# DCtoAC_Schematic.net
KiCad netlist of a schematic drawn in Altium Designer
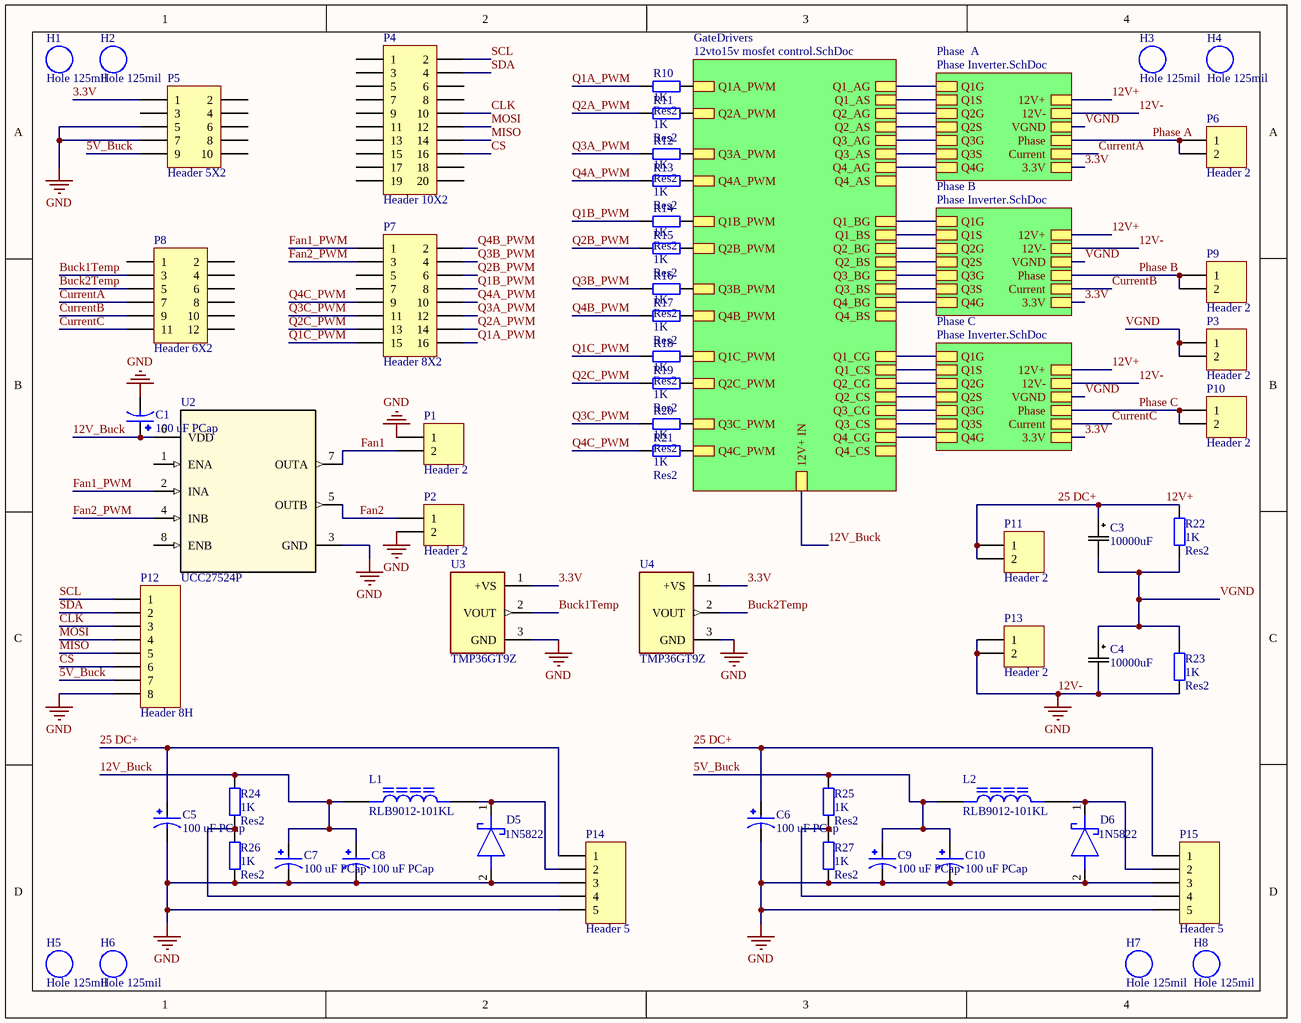
[diagram p0: DCtoAC Schematic.SchDoc]

(export (version "E")
  (design (tool "Eeschema 10.0.6"))
  (components
    (comp (ref "C1")
      (value "100 uF PCap")
      (footprint "Senior Design PCB Library:100uF PCap")
      (description "Capacitor; Aluminum Electrolytic; Radial Al Electrolytic Cap; 100uF 63V")
      (fields (field (name "MF") "Panasonic Electronic") (field (name "MP") "EEU-FC1J101"))
      (libsource (lib "") (part "100 uF PCap_1"))
    )
    (comp (ref "C3")
      (value "10000uF")
      (footprint "Senior Design PCB Library:CAP_UBY_18X35P5_NCH")
      (description "No Description Available")
      (libsource (lib "Senior Design Schematic Library") (part "10000uF"))
    )
    (comp (ref "C4")
      (value "10000uF")
      (footprint "Senior Design PCB Library:CAP_UBY_18X35P5_NCH")
      (description "No Description Available")
      (libsource (lib "Senior Design Schematic Library") (part "10000uF"))
    )
    (comp (ref "C5")
      (value "100 uF PCap")
      (footprint "Senior Design PCB Library:100uF PCap")
      (description "Capacitor; Aluminum Electrolytic; Radial Al Electrolytic Cap; 100uF 63V")
      (fields (field (name "MF") "Panasonic Electronic") (field (name "MP") "EEU-FC1J101"))
      (libsource (lib "Senior Design Schematic Library") (part "100 uF PCap"))
    )
    (comp (ref "C6")
      (value "100 uF PCap")
      (footprint "Senior Design PCB Library:100uF PCap")
      (description "Capacitor; Aluminum Electrolytic; Radial Al Electrolytic Cap; 100uF 63V")
      (fields (field (name "MF") "Panasonic Electronic") (field (name "MP") "EEU-FC1J101"))
      (libsource (lib "Senior Design Schematic Library") (part "100 uF PCap"))
    )
    (comp (ref "C7")
      (value "100 uF PCap")
      (footprint "Senior Design PCB Library:100uF PCap")
      (description "Capacitor; Aluminum Electrolytic; Radial Al Electrolytic Cap; 100uF 63V")
      (fields (field (name "MF") "Panasonic Electronic") (field (name "MP") "EEU-FC1J101"))
      (libsource (lib "Senior Design Schematic Library") (part "100 uF PCap"))
    )
    (comp (ref "C8")
      (value "100 uF PCap")
      (footprint "Senior Design PCB Library:100uF PCap")
      (description "Capacitor; Aluminum Electrolytic; Radial Al Electrolytic Cap; 100uF 63V")
      (fields (field (name "MF") "Panasonic Electronic") (field (name "MP") "EEU-FC1J101"))
      (libsource (lib "Senior Design Schematic Library") (part "100 uF PCap"))
    )
    (comp (ref "C9")
      (value "100 uF PCap")
      (footprint "Senior Design PCB Library:100uF PCap")
      (description "Capacitor; Aluminum Electrolytic; Radial Al Electrolytic Cap; 100uF 63V")
      (fields (field (name "MF") "Panasonic Electronic") (field (name "MP") "EEU-FC1J101"))
      (libsource (lib "Senior Design Schematic Library") (part "100 uF PCap"))
    )
    (comp (ref "C10")
      (value "100 uF PCap")
      (footprint "Senior Design PCB Library:100uF PCap")
      (description "Capacitor; Aluminum Electrolytic; Radial Al Electrolytic Cap; 100uF 63V")
      (fields (field (name "MF") "Panasonic Electronic") (field (name "MP") "EEU-FC1J101"))
      (libsource (lib "Senior Design Schematic Library") (part "100 uF PCap"))
    )
    (comp (ref "D5")
      (value "1N5822")
      (footprint "DIOAD3070W130L950D530")
      (description "Schottky Diode")
      (fields (field (name "MOUSER PART NUMBER") "511-1N5822"))
      (libsource (lib "Senior Design Schematic Library") (part "1N5822"))
    )
    (comp (ref "D6")
      (value "1N5822")
      (footprint "DIOAD3070W130L950D530")
      (description "Schottky Diode")
      (fields (field (name "MOUSER PART NUMBER") "511-1N5822"))
      (libsource (lib "Senior Design Schematic Library") (part "1N5822"))
    )
    (comp (ref "H1")
      (value "Hole 125mil")
      (footprint "Hole 125mil")
      (libsource (lib "ECE Lib 22") (part "Hole 125mil"))
    )
    (comp (ref "H2")
      (value "Hole 125mil")
      (footprint "Hole 125mil")
      (libsource (lib "ECE Lib 22") (part "Hole 125mil"))
    )
    (comp (ref "H3")
      (value "Hole 125mil")
      (footprint "Hole 125mil")
      (libsource (lib "ECE Lib 22") (part "Hole 125mil"))
    )
    (comp (ref "H4")
      (value "Hole 125mil")
      (footprint "Hole 125mil")
      (libsource (lib "ECE Lib 22") (part "Hole 125mil"))
    )
    (comp (ref "H5")
      (value "Hole 125mil")
      (footprint "Hole 125mil")
      (libsource (lib "ECE Lib 22") (part "Hole 125mil"))
    )
    (comp (ref "H6")
      (value "Hole 125mil")
      (footprint "Hole 125mil")
      (libsource (lib "ECE Lib 22") (part "Hole 125mil"))
    )
    (comp (ref "H7")
      (value "Hole 125mil")
      (footprint "Hole 125mil")
      (libsource (lib "ECE Lib 22") (part "Hole 125mil"))
    )
    (comp (ref "H8")
      (value "Hole 125mil")
      (footprint "Hole 125mil")
      (libsource (lib "ECE Lib 22") (part "Hole 125mil"))
    )
    (comp (ref "L1")
      (value "RLB9012-101KL")
      (footprint "Senior Design PCB Library:IND_RLB9012-101KL")
      (libsource (lib "Senior Design Schematic Library") (part "RLB9012-101KL"))
    )
    (comp (ref "L2")
      (value "RLB9012-101KL")
      (footprint "Senior Design PCB Library:IND_RLB9012-101KL")
      (libsource (lib "Senior Design Schematic Library") (part "RLB9012-101KL"))
    )
    (comp (ref "P1")
      (value "Header 2")
      (footprint "HDR1X2")
      (description "Header, 2-Pin")
      (fields (field (name "PUBLISHER") "Altium Limited"))
      (libsource (lib "Miscellaneous Connectors") (part "Header 2"))
    )
    (comp (ref "P2")
      (value "Header 2")
      (footprint "HDR1X2")
      (description "Header, 2-Pin")
      (fields (field (name "PUBLISHER") "Altium Limited"))
      (libsource (lib "Miscellaneous Connectors") (part "Header 2"))
    )
    (comp (ref "P3")
      (value "Header 2")
      (footprint "HDR1X2")
      (description "Header, 2-Pin")
      (fields (field (name "PUBLISHER") "Altium Limited"))
      (libsource (lib "Miscellaneous Connectors") (part "Header 2"))
    )
    (comp (ref "P4")
      (value "Header 10X2")
      (footprint "HDR2X10")
      (description "Header, 10-Pin, Dual row")
      (fields (field (name "PUBLISHER") "Altium Limited"))
      (libsource (lib "Miscellaneous Connectors") (part "Header 10X2"))
    )
    (comp (ref "P5")
      (value "Header 5X2")
      (footprint "HDR2X5")
      (description "Header, 5-Pin, Dual row")
      (fields (field (name "PUBLISHER") "Altium Limited"))
      (libsource (lib "Miscellaneous Connectors") (part "Header 5X2"))
    )
    (comp (ref "P6")
      (value "Header 2")
      (footprint "HDR1X2")
      (description "Header, 2-Pin")
      (fields (field (name "PUBLISHER") "Altium Limited"))
      (libsource (lib "Miscellaneous Connectors") (part "Header 2"))
    )
    (comp (ref "P7")
      (value "Header 8X2")
      (footprint "HDR2X8")
      (description "Header, 8-Pin, Dual row")
      (fields (field (name "PUBLISHER") "Altium Limited"))
      (libsource (lib "Miscellaneous Connectors") (part "Header 8X2"))
    )
    (comp (ref "P8")
      (value "Header 6X2")
      (footprint "HDR2X6")
      (description "Header, 6-Pin, Dual row")
      (fields (field (name "PUBLISHER") "Altium Limited"))
      (libsource (lib "Miscellaneous Connectors") (part "Header 6X2"))
    )
    (comp (ref "P9")
      (value "Header 2")
      (footprint "HDR1X2")
      (description "Header, 2-Pin")
      (fields (field (name "PUBLISHER") "Altium Limited"))
      (libsource (lib "Miscellaneous Connectors") (part "Header 2"))
    )
    (comp (ref "P10")
      (value "Header 2")
      (footprint "HDR1X2")
      (description "Header, 2-Pin")
      (fields (field (name "PUBLISHER") "Altium Limited"))
      (libsource (lib "Miscellaneous Connectors") (part "Header 2"))
    )
    (comp (ref "P11")
      (value "Header 2")
      (footprint "HDR1X2")
      (description "Header, 2-Pin")
      (fields (field (name "PUBLISHER") "Altium Limited"))
      (libsource (lib "Miscellaneous Connectors") (part "Header 2"))
    )
    (comp (ref "P12")
      (value "Header 8H")
      (footprint "HDR1X8H")
      (description "Header, 8-Pin, Right Angle")
      (fields (field (name "PUBLISHER") "Altium Limited"))
      (libsource (lib "Miscellaneous Connectors") (part "Header 8H"))
    )
    (comp (ref "P13")
      (value "Header 2")
      (footprint "HDR1X2")
      (description "Header, 2-Pin")
      (fields (field (name "PUBLISHER") "Altium Limited"))
      (libsource (lib "Miscellaneous Connectors") (part "Header 2"))
    )
    (comp (ref "P14")
      (value "Header 5")
      (footprint "HDR1X5")
      (description "Header, 5-Pin")
      (fields (field (name "PUBLISHER") "Altium Limited"))
      (libsource (lib "Miscellaneous Connectors") (part "Header 5"))
    )
    (comp (ref "P15")
      (value "Header 5")
      (footprint "HDR1X5")
      (description "Header, 5-Pin")
      (fields (field (name "PUBLISHER") "Altium Limited"))
      (libsource (lib "Miscellaneous Connectors") (part "Header 5"))
    )
    (comp (ref "R10")
      (value "Res2")
      (footprint "AXIAL-0.4")
      (description "Resistor")
      (fields (field (name "ALTIUM_VALUE") "1K") (field (name "PUBLISHER") "Altium Limited"))
      (libsource (lib "") (part "Res2_2"))
    )
    (comp (ref "R11")
      (value "Res2")
      (footprint "AXIAL-0.4")
      (description "Resistor")
      (fields (field (name "ALTIUM_VALUE") "1K") (field (name "PUBLISHER") "Altium Limited"))
      (libsource (lib "") (part "Res2_2"))
    )
    (comp (ref "R12")
      (value "Res2")
      (footprint "AXIAL-0.4")
      (description "Resistor")
      (fields (field (name "ALTIUM_VALUE") "1K") (field (name "PUBLISHER") "Altium Limited"))
      (libsource (lib "") (part "Res2_2"))
    )
    (comp (ref "R13")
      (value "Res2")
      (footprint "AXIAL-0.4")
      (description "Resistor")
      (fields (field (name "ALTIUM_VALUE") "1K") (field (name "PUBLISHER") "Altium Limited"))
      (libsource (lib "") (part "Res2_2"))
    )
    (comp (ref "R14")
      (value "Res2")
      (footprint "AXIAL-0.4")
      (description "Resistor")
      (fields (field (name "ALTIUM_VALUE") "1K") (field (name "PUBLISHER") "Altium Limited"))
      (libsource (lib "") (part "Res2_2"))
    )
    (comp (ref "R15")
      (value "Res2")
      (footprint "AXIAL-0.4")
      (description "Resistor")
      (fields (field (name "ALTIUM_VALUE") "1K") (field (name "PUBLISHER") "Altium Limited"))
      (libsource (lib "") (part "Res2_2"))
    )
    (comp (ref "R16")
      (value "Res2")
      (footprint "AXIAL-0.4")
      (description "Resistor")
      (fields (field (name "ALTIUM_VALUE") "1K") (field (name "PUBLISHER") "Altium Limited"))
      (libsource (lib "") (part "Res2_2"))
    )
    (comp (ref "R17")
      (value "Res2")
      (footprint "AXIAL-0.4")
      (description "Resistor")
      (fields (field (name "ALTIUM_VALUE") "1K") (field (name "PUBLISHER") "Altium Limited"))
      (libsource (lib "") (part "Res2_2"))
    )
    (comp (ref "R18")
      (value "Res2")
      (footprint "AXIAL-0.4")
      (description "Resistor")
      (fields (field (name "ALTIUM_VALUE") "1K") (field (name "PUBLISHER") "Altium Limited"))
      (libsource (lib "") (part "Res2_2"))
    )
    (comp (ref "R19")
      (value "Res2")
      (footprint "AXIAL-0.4")
      (description "Resistor")
      (fields (field (name "ALTIUM_VALUE") "1K") (field (name "PUBLISHER") "Altium Limited"))
      (libsource (lib "") (part "Res2_2"))
    )
    (comp (ref "R20")
      (value "Res2")
      (footprint "AXIAL-0.4")
      (description "Resistor")
      (fields (field (name "ALTIUM_VALUE") "1K") (field (name "PUBLISHER") "Altium Limited"))
      (libsource (lib "") (part "Res2_2"))
    )
    (comp (ref "R21")
      (value "Res2")
      (footprint "AXIAL-0.4")
      (description "Resistor")
      (fields (field (name "ALTIUM_VALUE") "1K") (field (name "PUBLISHER") "Altium Limited"))
      (libsource (lib "") (part "Res2_2"))
    )
    (comp (ref "R22")
      (value "Res2")
      (footprint "AXIAL-0.4")
      (description "Resistor")
      (fields (field (name "ALTIUM_VALUE") "1K") (field (name "PUBLISHER") "Altium Limited"))
      (libsource (lib "Miscellaneous Devices") (part "Res2"))
    )
    (comp (ref "R23")
      (value "Res2")
      (footprint "AXIAL-0.4")
      (description "Resistor")
      (fields (field (name "ALTIUM_VALUE") "1K") (field (name "PUBLISHER") "Altium Limited"))
      (libsource (lib "Miscellaneous Devices") (part "Res2"))
    )
    (comp (ref "R24")
      (value "Res2")
      (footprint "AXIAL-0.4")
      (description "Resistor")
      (fields (field (name "ALTIUM_VALUE") "1K") (field (name "PUBLISHER") "Altium Limited"))
      (libsource (lib "") (part "Res2_1"))
    )
    (comp (ref "R25")
      (value "Res2")
      (footprint "AXIAL-0.4")
      (description "Resistor")
      (fields (field (name "ALTIUM_VALUE") "1K") (field (name "PUBLISHER") "Altium Limited"))
      (libsource (lib "") (part "Res2_1"))
    )
    (comp (ref "R26")
      (value "Res2")
      (footprint "AXIAL-0.4")
      (description "Resistor")
      (fields (field (name "ALTIUM_VALUE") "1K") (field (name "PUBLISHER") "Altium Limited"))
      (libsource (lib "") (part "Res2_1"))
    )
    (comp (ref "R27")
      (value "Res2")
      (footprint "AXIAL-0.4")
      (description "Resistor")
      (fields (field (name "ALTIUM_VALUE") "1K") (field (name "PUBLISHER") "Altium Limited"))
      (libsource (lib "") (part "Res2_1"))
    )
    (comp (ref "U2")
      (value "UCC27524P")
      (footprint "Senior Design PCB Library:P0008A")
      (description "IC Gate")
      (libsource (lib "Senior Design Schematic Library") (part "UCC27524P"))
    )
    (comp (ref "U3")
      (value "TMP36GT9Z")
      (footprint "Senior Design PCB Library:TO92127P521H733-3")
      (description "Voltage Output Temperature Sensors")
      (fields (field (name "MF") "Analog Devices"))
      (libsource (lib "Senior Design Schematic Library") (part "TMP36GT9Z"))
    )
    (comp (ref "U4")
      (value "TMP36GT9Z")
      (footprint "Senior Design PCB Library:TO92127P521H733-3")
      (description "Voltage Output Temperature Sensors")
      (fields (field (name "MF") "Analog Devices"))
      (libsource (lib "Senior Design Schematic Library") (part "TMP36GT9Z"))
    )
  )
  (nets
    (net (code "1") (name "/3.3V") (class "Default")
      (node (ref "P5") (pin "1") (pinfunction "1_1") (pintype "passive"))
      (node (ref "U3") (pin "1") (pinfunction "+VS_1") (pintype "power_in"))
      (node (ref "U4") (pin "1") (pinfunction "+VS_1") (pintype "power_in"))
    )
    (net (code "2") (name "/5V_Buck") (class "Default")
      (node (ref "C10") (pin "P") (pinfunction "P_P") (pintype "passive"))
      (node (ref "C9") (pin "P") (pinfunction "P_P") (pintype "passive"))
      (node (ref "L2") (pin "1") (pinfunction "1_1") (pintype "passive"))
      (node (ref "P12") (pin "7") (pinfunction "7_7") (pintype "passive"))
      (node (ref "P5") (pin "9") (pinfunction "9_9") (pintype "passive"))
      (node (ref "R25") (pin "1") (pinfunction "1_1") (pintype "passive"))
    )
    (net (code "3") (name "/12V+") (class "Default")
      (node (ref "C3") (pin "1") (pinfunction "1_1") (pintype "passive"))
      (node (ref "C5") (pin "P") (pinfunction "P_P") (pintype "passive"))
      (node (ref "C6") (pin "P") (pinfunction "P_P") (pintype "passive"))
      (node (ref "P11") (pin "1") (pinfunction "1_1") (pintype "passive"))
      (node (ref "P11") (pin "2") (pinfunction "2_2") (pintype "passive"))
      (node (ref "P14") (pin "1") (pinfunction "1_1") (pintype "passive"))
      (node (ref "P15") (pin "1") (pinfunction "1_1") (pintype "passive"))
      (node (ref "R22") (pin "2") (pinfunction "2_2") (pintype "passive"))
    )
    (net (code "4") (name "/12V_Buck") (class "Default")
      (node (ref "C1") (pin "P") (pinfunction "P_P") (pintype "passive"))
      (node (ref "C7") (pin "P") (pinfunction "P_P") (pintype "passive"))
      (node (ref "C8") (pin "P") (pinfunction "P_P") (pintype "passive"))
      (node (ref "L1") (pin "1") (pinfunction "1_1") (pintype "passive"))
      (node (ref "R24") (pin "1") (pinfunction "1_1") (pintype "passive"))
      (node (ref "U2") (pin "6") (pinfunction "VDD_6") (pintype "power_in"))
    )
    (net (code "5") (name "/Buck1Temp") (class "Default")
      (node (ref "P8") (pin "3") (pinfunction "3_3") (pintype "passive"))
      (node (ref "U3") (pin "2") (pinfunction "VOUT_2") (pintype "output"))
    )
    (net (code "6") (name "/Buck2Temp") (class "Default")
      (node (ref "P8") (pin "5") (pinfunction "5_5") (pintype "passive"))
      (node (ref "U4") (pin "2") (pinfunction "VOUT_2") (pintype "output"))
    )
    (net (code "7") (name "/CLK") (class "Default")
      (node (ref "P12") (pin "3") (pinfunction "3_3") (pintype "passive"))
      (node (ref "P4") (pin "10") (pinfunction "10_10") (pintype "passive"))
    )
    (net (code "8") (name "/CS") (class "Default")
      (node (ref "P12") (pin "6") (pinfunction "6_6") (pintype "passive"))
      (node (ref "P4") (pin "16") (pinfunction "16_16") (pintype "passive"))
    )
    (net (code "9") (name "/CurrentA") (class "Default")
      (node (ref "P8") (pin "7") (pinfunction "7_7") (pintype "passive"))
    )
    (net (code "10") (name "/CurrentB") (class "Default")
      (node (ref "P8") (pin "9") (pinfunction "9_9") (pintype "passive"))
    )
    (net (code "11") (name "/CurrentC") (class "Default")
      (node (ref "P8") (pin "11") (pinfunction "11_11") (pintype "passive"))
    )
    (net (code "12") (name "/Fan1") (class "Default")
      (node (ref "P1") (pin "2") (pinfunction "2_2") (pintype "passive"))
      (node (ref "U2") (pin "7") (pinfunction "OUTA_7") (pintype "output"))
    )
    (net (code "13") (name "/Fan1_PWM") (class "Default")
      (node (ref "P7") (pin "1") (pinfunction "1_1") (pintype "passive"))
      (node (ref "U2") (pin "2") (pinfunction "INA_2") (pintype "input"))
    )
    (net (code "14") (name "/Fan2") (class "Default")
      (node (ref "P2") (pin "1") (pinfunction "1_1") (pintype "passive"))
      (node (ref "U2") (pin "5") (pinfunction "OUTB_5") (pintype "output"))
    )
    (net (code "15") (name "/Fan2_PWM") (class "Default")
      (node (ref "P7") (pin "3") (pinfunction "3_3") (pintype "passive"))
      (node (ref "U2") (pin "4") (pinfunction "INB_4") (pintype "input"))
    )
    (net (code "16") (name "/MISO") (class "Default")
      (node (ref "P12") (pin "5") (pinfunction "5_5") (pintype "passive"))
      (node (ref "P4") (pin "14") (pinfunction "14_14") (pintype "passive"))
    )
    (net (code "17") (name "/MOSI") (class "Default")
      (node (ref "P12") (pin "4") (pinfunction "4_4") (pintype "passive"))
      (node (ref "P4") (pin "12") (pinfunction "12_12") (pintype "passive"))
    )
    (net (code "18") (name "/Phase A") (class "Default")
      (node (ref "P6") (pin "1") (pinfunction "1_1") (pintype "passive"))
      (node (ref "P6") (pin "2") (pinfunction "2_2") (pintype "passive"))
    )
    (net (code "19") (name "/Phase B") (class "Default")
      (node (ref "P9") (pin "1") (pinfunction "1_1") (pintype "passive"))
      (node (ref "P9") (pin "2") (pinfunction "2_2") (pintype "passive"))
    )
    (net (code "20") (name "/Phase C") (class "Default")
      (node (ref "P10") (pin "1") (pinfunction "1_1") (pintype "passive"))
      (node (ref "P10") (pin "2") (pinfunction "2_2") (pintype "passive"))
    )
    (net (code "21") (name "/Q1A_PWM") (class "Default")
      (node (ref "P7") (pin "16") (pinfunction "16_16") (pintype "passive"))
      (node (ref "R10") (pin "1") (pinfunction "1_1") (pintype "passive"))
    )
    (net (code "22") (name "/Q1A_PWM_1") (class "Default")
      (node (ref "R10") (pin "2") (pinfunction "2_2") (pintype "passive"))
    )
    (net (code "23") (name "/Q1B_PWM") (class "Default")
      (node (ref "P7") (pin "8") (pinfunction "8_8") (pintype "passive"))
      (node (ref "R14") (pin "1") (pinfunction "1_1") (pintype "passive"))
    )
    (net (code "24") (name "/Q1B_PWM_1") (class "Default")
      (node (ref "R14") (pin "2") (pinfunction "2_2") (pintype "passive"))
    )
    (net (code "25") (name "/Q1C_PWM") (class "Default")
      (node (ref "P7") (pin "15") (pinfunction "15_15") (pintype "passive"))
      (node (ref "R18") (pin "1") (pinfunction "1_1") (pintype "passive"))
    )
    (net (code "26") (name "/Q1C_PWM_1") (class "Default")
      (node (ref "R18") (pin "2") (pinfunction "2_2") (pintype "passive"))
    )
    (net (code "33") (name "/Q2A_PWM") (class "Default")
      (node (ref "P7") (pin "14") (pinfunction "14_14") (pintype "passive"))
      (node (ref "R11") (pin "1") (pinfunction "1_1") (pintype "passive"))
    )
    (net (code "34") (name "/Q2A_PWM_1") (class "Default")
      (node (ref "R11") (pin "2") (pinfunction "2_2") (pintype "passive"))
    )
    (net (code "35") (name "/Q2B_PWM") (class "Default")
      (node (ref "P7") (pin "6") (pinfunction "6_6") (pintype "passive"))
      (node (ref "R15") (pin "1") (pinfunction "1_1") (pintype "passive"))
    )
    (net (code "36") (name "/Q2B_PWM_1") (class "Default")
      (node (ref "R15") (pin "2") (pinfunction "2_2") (pintype "passive"))
    )
    (net (code "37") (name "/Q2C_PWM") (class "Default")
      (node (ref "P7") (pin "13") (pinfunction "13_13") (pintype "passive"))
      (node (ref "R19") (pin "1") (pinfunction "1_1") (pintype "passive"))
    )
    (net (code "38") (name "/Q2C_PWM_1") (class "Default")
      (node (ref "R19") (pin "2") (pinfunction "2_2") (pintype "passive"))
    )
    (net (code "45") (name "/Q3A_PWM") (class "Default")
      (node (ref "P7") (pin "12") (pinfunction "12_12") (pintype "passive"))
      (node (ref "R12") (pin "1") (pinfunction "1_1") (pintype "passive"))
    )
    (net (code "46") (name "/Q3A_PWM_1") (class "Default")
      (node (ref "R12") (pin "2") (pinfunction "2_2") (pintype "passive"))
    )
    (net (code "47") (name "/Q3B_PWM") (class "Default")
      (node (ref "P7") (pin "4") (pinfunction "4_4") (pintype "passive"))
      (node (ref "R16") (pin "1") (pinfunction "1_1") (pintype "passive"))
    )
    (net (code "48") (name "/Q3B_PWM_1") (class "Default")
      (node (ref "R16") (pin "2") (pinfunction "2_2") (pintype "passive"))
    )
    (net (code "49") (name "/Q3C_PWM") (class "Default")
      (node (ref "P7") (pin "11") (pinfunction "11_11") (pintype "passive"))
      (node (ref "R20") (pin "1") (pinfunction "1_1") (pintype "passive"))
    )
    (net (code "50") (name "/Q3C_PWM_1") (class "Default")
      (node (ref "R20") (pin "2") (pinfunction "2_2") (pintype "passive"))
    )
    (net (code "57") (name "/Q4A_PWM") (class "Default")
      (node (ref "P7") (pin "10") (pinfunction "10_10") (pintype "passive"))
      (node (ref "R13") (pin "1") (pinfunction "1_1") (pintype "passive"))
    )
    (net (code "58") (name "/Q4A_PWM_1") (class "Default")
      (node (ref "R13") (pin "2") (pinfunction "2_2") (pintype "passive"))
    )
    (net (code "59") (name "/Q4B_PWM") (class "Default")
      (node (ref "P7") (pin "2") (pinfunction "2_2") (pintype "passive"))
      (node (ref "R17") (pin "1") (pinfunction "1_1") (pintype "passive"))
    )
    (net (code "60") (name "/Q4B_PWM_1") (class "Default")
      (node (ref "R17") (pin "2") (pinfunction "2_2") (pintype "passive"))
    )
    (net (code "61") (name "/Q4C_PWM") (class "Default")
      (node (ref "P7") (pin "9") (pinfunction "9_9") (pintype "passive"))
      (node (ref "R21") (pin "1") (pinfunction "1_1") (pintype "passive"))
    )
    (net (code "62") (name "/Q4C_PWM_1") (class "Default")
      (node (ref "R21") (pin "2") (pinfunction "2_2") (pintype "passive"))
    )
    (net (code "69") (name "/SCL") (class "Default")
      (node (ref "P12") (pin "1") (pinfunction "1_1") (pintype "passive"))
      (node (ref "P4") (pin "2") (pinfunction "2_2") (pintype "passive"))
    )
    (net (code "70") (name "/SDA") (class "Default")
      (node (ref "P12") (pin "2") (pinfunction "2_2") (pintype "passive"))
      (node (ref "P4") (pin "4") (pinfunction "4_4") (pintype "passive"))
    )
    (net (code "71") (name "/VGND") (class "Default")
      (node (ref "C3") (pin "2") (pinfunction "2_2") (pintype "passive"))
      (node (ref "C4") (pin "1") (pinfunction "1_1") (pintype "passive"))
      (node (ref "P3") (pin "1") (pinfunction "1_1") (pintype "passive"))
      (node (ref "P3") (pin "2") (pinfunction "2_2") (pintype "passive"))
      (node (ref "R22") (pin "1") (pinfunction "1_1") (pintype "passive"))
      (node (ref "R23") (pin "2") (pinfunction "2_2") (pintype "passive"))
    )
    (net (code "72") (name "GND") (class "Default")
      (node (ref "C1") (pin "N") (pinfunction "N_N") (pintype "passive"))
      (node (ref "C10") (pin "N") (pinfunction "N_N") (pintype "passive"))
      (node (ref "C4") (pin "2") (pinfunction "2_2") (pintype "passive"))
      (node (ref "C5") (pin "N") (pinfunction "N_N") (pintype "passive"))
      (node (ref "C6") (pin "N") (pinfunction "N_N") (pintype "passive"))
      (node (ref "C7") (pin "N") (pinfunction "N_N") (pintype "passive"))
      (node (ref "C8") (pin "N") (pinfunction "N_N") (pintype "passive"))
      (node (ref "C9") (pin "N") (pinfunction "N_N") (pintype "passive"))
      (node (ref "D5") (pin "2") (pinfunction "A_2") (pintype "passive"))
      (node (ref "D6") (pin "2") (pinfunction "A_2") (pintype "passive"))
      (node (ref "P1") (pin "1") (pinfunction "1_1") (pintype "passive"))
      (node (ref "P12") (pin "8") (pinfunction "8_8") (pintype "passive"))
      (node (ref "P13") (pin "1") (pinfunction "1_1") (pintype "passive"))
      (node (ref "P13") (pin "2") (pinfunction "2_2") (pintype "passive"))
      (node (ref "P14") (pin "3") (pinfunction "3_3") (pintype "passive"))
      (node (ref "P14") (pin "5") (pinfunction "5_5") (pintype "passive"))
      (node (ref "P15") (pin "3") (pinfunction "3_3") (pintype "passive"))
      (node (ref "P15") (pin "5") (pinfunction "5_5") (pintype "passive"))
      (node (ref "P2") (pin "2") (pinfunction "2_2") (pintype "passive"))
      (node (ref "P5") (pin "5") (pinfunction "5_5") (pintype "passive"))
      (node (ref "P5") (pin "7") (pinfunction "7_7") (pintype "passive"))
      (node (ref "R23") (pin "1") (pinfunction "1_1") (pintype "passive"))
      (node (ref "R26") (pin "2") (pinfunction "2_2") (pintype "passive"))
      (node (ref "R27") (pin "2") (pinfunction "2_2") (pintype "passive"))
      (node (ref "U2") (pin "3") (pinfunction "GND_3") (pintype "power_in"))
      (node (ref "U3") (pin "3") (pinfunction "GND_3") (pintype "power_in"))
      (node (ref "U4") (pin "3") (pinfunction "GND_3") (pintype "power_in"))
    )
    (net (code "73") (name "Net-(D5-K)") (class "Default")
      (node (ref "D5") (pin "1") (pinfunction "K_1") (pintype "passive"))
      (node (ref "L1") (pin "2") (pinfunction "2_2") (pintype "passive"))
      (node (ref "P14") (pin "2") (pinfunction "2_2") (pintype "passive"))
    )
    (net (code "74") (name "Net-(D6-K)") (class "Default")
      (node (ref "D6") (pin "1") (pinfunction "K_1") (pintype "passive"))
      (node (ref "L2") (pin "2") (pinfunction "2_2") (pintype "passive"))
      (node (ref "P15") (pin "2") (pinfunction "2_2") (pintype "passive"))
    )
    (net (code "75") (name "Net-(P14-Pad4)") (class "Default")
      (node (ref "P14") (pin "4") (pinfunction "4_4") (pintype "passive"))
      (node (ref "R24") (pin "2") (pinfunction "2_2") (pintype "passive"))
      (node (ref "R26") (pin "1") (pinfunction "1_1") (pintype "passive"))
    )
    (net (code "76") (name "Net-(P15-Pad4)") (class "Default")
      (node (ref "P15") (pin "4") (pinfunction "4_4") (pintype "passive"))
      (node (ref "R25") (pin "2") (pinfunction "2_2") (pintype "passive"))
      (node (ref "R27") (pin "1") (pinfunction "1_1") (pintype "passive"))
    )
    (net (code "77") (name "unconnected-(P4-Pad1)") (class "Default")
      (node (ref "P4") (pin "1") (pinfunction "1_1") (pintype "passive"))
    )
    (net (code "78") (name "unconnected-(P4-Pad3)") (class "Default")
      (node (ref "P4") (pin "3") (pinfunction "3_3") (pintype "passive"))
    )
    (net (code "79") (name "unconnected-(P4-Pad5)") (class "Default")
      (node (ref "P4") (pin "5") (pinfunction "5_5") (pintype "passive"))
    )
    (net (code "80") (name "unconnected-(P4-Pad6)") (class "Default")
      (node (ref "P4") (pin "6") (pinfunction "6_6") (pintype "passive"))
    )
    (net (code "81") (name "unconnected-(P4-Pad7)") (class "Default")
      (node (ref "P4") (pin "7") (pinfunction "7_7") (pintype "passive"))
    )
    (net (code "82") (name "unconnected-(P4-Pad8)") (class "Default")
      (node (ref "P4") (pin "8") (pinfunction "8_8") (pintype "passive"))
    )
    (net (code "83") (name "unconnected-(P4-Pad9)") (class "Default")
      (node (ref "P4") (pin "9") (pinfunction "9_9") (pintype "passive"))
    )
    (net (code "84") (name "unconnected-(P4-Pad11)") (class "Default")
      (node (ref "P4") (pin "11") (pinfunction "11_11") (pintype "passive"))
    )
    (net (code "85") (name "unconnected-(P4-Pad13)") (class "Default")
      (node (ref "P4") (pin "13") (pinfunction "13_13") (pintype "passive"))
    )
    (net (code "86") (name "unconnected-(P4-Pad15)") (class "Default")
      (node (ref "P4") (pin "15") (pinfunction "15_15") (pintype "passive"))
    )
    (net (code "87") (name "unconnected-(P4-Pad17)") (class "Default")
      (node (ref "P4") (pin "17") (pinfunction "17_17") (pintype "passive"))
    )
    (net (code "88") (name "unconnected-(P4-Pad18)") (class "Default")
      (node (ref "P4") (pin "18") (pinfunction "18_18") (pintype "passive"))
    )
    (net (code "89") (name "unconnected-(P4-Pad19)") (class "Default")
      (node (ref "P4") (pin "19") (pinfunction "19_19") (pintype "passive"))
    )
    (net (code "90") (name "unconnected-(P4-Pad20)") (class "Default")
      (node (ref "P4") (pin "20") (pinfunction "20_20") (pintype "passive"))
    )
    (net (code "91") (name "unconnected-(P5-Pad2)") (class "Default")
      (node (ref "P5") (pin "2") (pinfunction "2_2") (pintype "passive"))
    )
    (net (code "92") (name "unconnected-(P5-Pad3)") (class "Default")
      (node (ref "P5") (pin "3") (pinfunction "3_3") (pintype "passive"))
    )
    (net (code "93") (name "unconnected-(P5-Pad4)") (class "Default")
      (node (ref "P5") (pin "4") (pinfunction "4_4") (pintype "passive"))
    )
    (net (code "94") (name "unconnected-(P5-Pad6)") (class "Default")
      (node (ref "P5") (pin "6") (pinfunction "6_6") (pintype "passive"))
    )
    (net (code "95") (name "unconnected-(P5-Pad8)") (class "Default")
      (node (ref "P5") (pin "8") (pinfunction "8_8") (pintype "passive"))
    )
    (net (code "96") (name "unconnected-(P5-Pad10)") (class "Default")
      (node (ref "P5") (pin "10") (pinfunction "10_10") (pintype "passive"))
    )
    (net (code "97") (name "unconnected-(P7-Pad5)") (class "Default")
      (node (ref "P7") (pin "5") (pinfunction "5_5") (pintype "passive"))
    )
    (net (code "98") (name "unconnected-(P7-Pad7)") (class "Default")
      (node (ref "P7") (pin "7") (pinfunction "7_7") (pintype "passive"))
    )
    (net (code "99") (name "unconnected-(P8-Pad1)") (class "Default")
      (node (ref "P8") (pin "1") (pinfunction "1_1") (pintype "passive"))
    )
    (net (code "100") (name "unconnected-(P8-Pad2)") (class "Default")
      (node (ref "P8") (pin "2") (pinfunction "2_2") (pintype "passive"))
    )
    (net (code "101") (name "unconnected-(P8-Pad4)") (class "Default")
      (node (ref "P8") (pin "4") (pinfunction "4_4") (pintype "passive"))
    )
    (net (code "102") (name "unconnected-(P8-Pad6)") (class "Default")
      (node (ref "P8") (pin "6") (pinfunction "6_6") (pintype "passive"))
    )
    (net (code "103") (name "unconnected-(P8-Pad8)") (class "Default")
      (node (ref "P8") (pin "8") (pinfunction "8_8") (pintype "passive"))
    )
    (net (code "104") (name "unconnected-(P8-Pad10)") (class "Default")
      (node (ref "P8") (pin "10") (pinfunction "10_10") (pintype "passive"))
    )
    (net (code "105") (name "unconnected-(P8-Pad12)") (class "Default")
      (node (ref "P8") (pin "12") (pinfunction "12_12") (pintype "passive"))
    )
    (net (code "106") (name "unconnected-(U2-ENA-Pad1)") (class "Default")
      (node (ref "U2") (pin "1") (pinfunction "ENA_1") (pintype "input"))
    )
    (net (code "107") (name "unconnected-(U2-ENB-Pad8)") (class "Default")
      (node (ref "U2") (pin "8") (pinfunction "ENB_8") (pintype "input"))
    )
  )
)
